# sch_Connet_IMU.net
KiCad netlist of a schematic drawn in Altium Designer
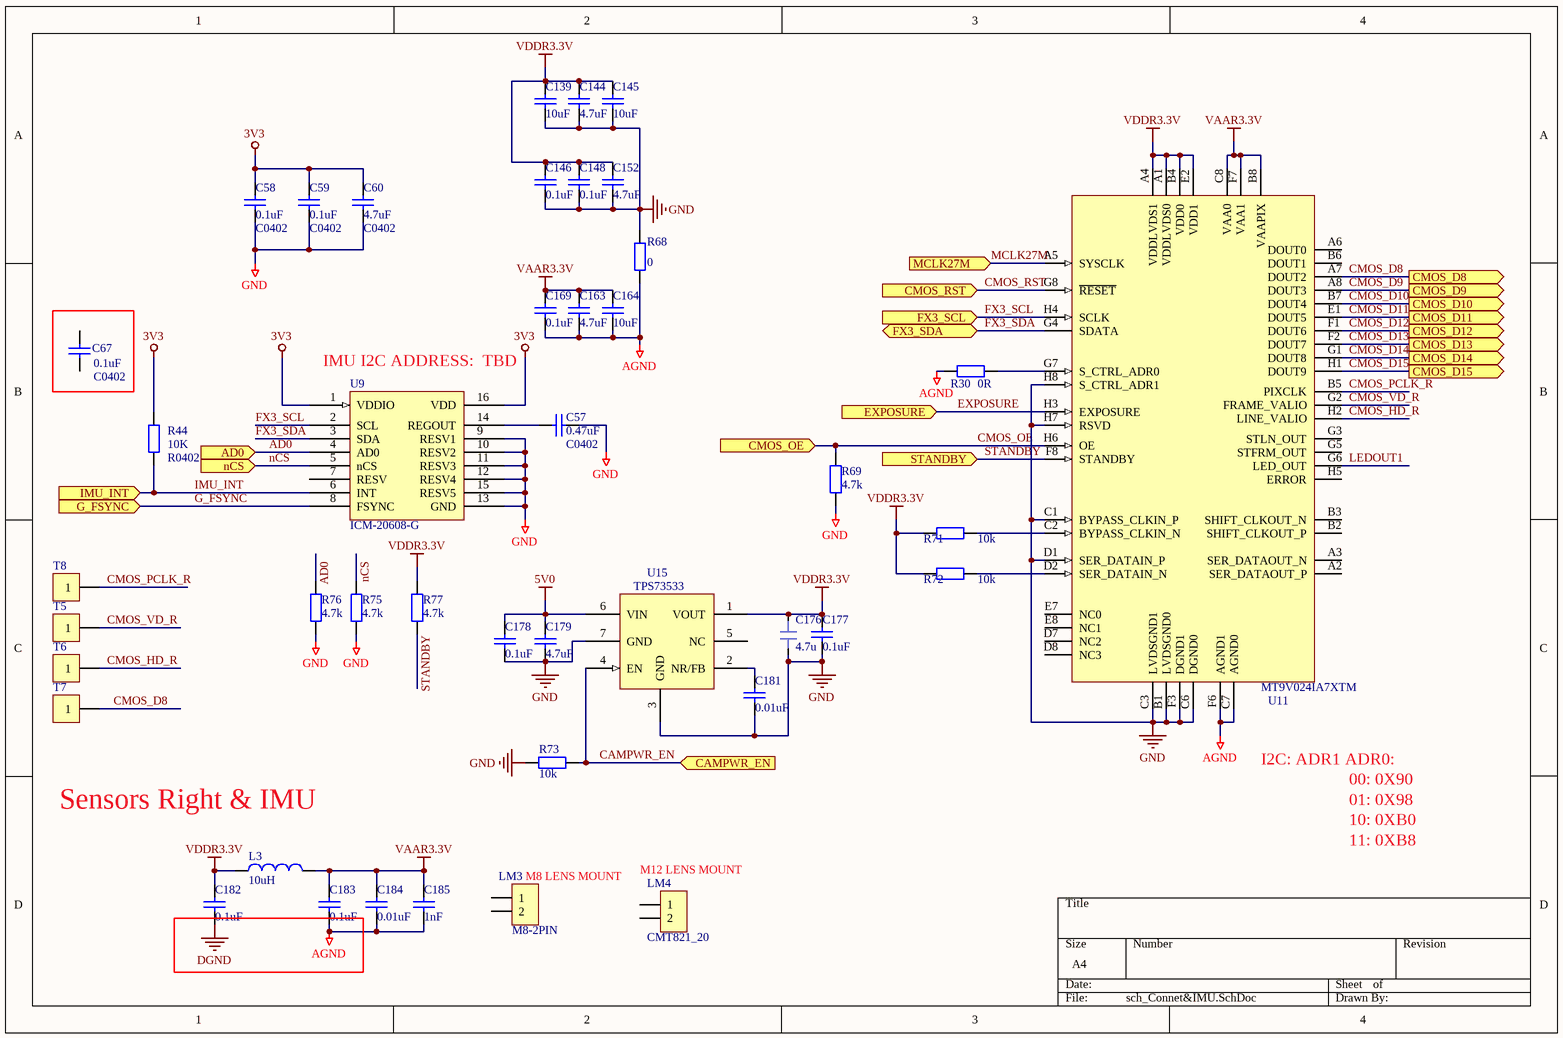
[diagram p0: sch_Connet&IMU.SchDoc]

(export (version "E")
  (design (tool "Eeschema 10.0.6"))
  (components
    (comp (ref "C57")
      (value "0.47uF")
      (footprint "0402C")
      (description "Capacitor")
      (fields (field (name "ALTIUM_VALUE") "C0402") (field (name "PUBLISHER") "Altium Limited"))
      (libsource (lib "Miscellaneous Devices") (part "Cap"))
    )
    (comp (ref "C58")
      (value "0.1uF")
      (footprint "0402C")
      (description "Capacitor")
      (fields (field (name "ALTIUM_VALUE") "C0402") (field (name "PUBLISHER") "Altium Limited"))
      (libsource (lib "Miscellaneous Devices") (part "Cap"))
    )
    (comp (ref "C59")
      (value "0.1uF")
      (footprint "0402C")
      (description "Capacitor")
      (fields (field (name "ALTIUM_VALUE") "C0402") (field (name "PUBLISHER") "Altium Limited"))
      (libsource (lib "Miscellaneous Devices") (part "Cap"))
    )
    (comp (ref "C60")
      (value "4.7uF")
      (footprint "0402C")
      (description "Capacitor")
      (fields (field (name "ALTIUM_VALUE") "C0402") (field (name "PUBLISHER") "Altium Limited"))
      (libsource (lib "Miscellaneous Devices") (part "Cap"))
    )
    (comp (ref "C67")
      (value "0.1uF")
      (footprint "0402C")
      (description "Capacitor")
      (fields (field (name "ALTIUM_VALUE") "C0402") (field (name "PUBLISHER") "Altium Limited"))
      (libsource (lib "Miscellaneous Devices") (part "Cap"))
    )
    (comp (ref "C139")
      (value "10uF")
      (footprint "0805C")
      (description "Capacitor")
      (fields (field (name "PUBLISHER") "Altium Limited"))
      (libsource (lib "Miscellaneous Devices") (part "Cap"))
    )
    (comp (ref "C144")
      (value "4.7uF")
      (footprint "0402C")
      (description "Capacitor")
      (fields (field (name "PUBLISHER") "Altium Limited"))
      (libsource (lib "Miscellaneous Devices") (part "Cap"))
    )
    (comp (ref "C145")
      (value "10uF")
      (footprint "0805C")
      (description "Capacitor")
      (fields (field (name "PUBLISHER") "Altium Limited"))
      (libsource (lib "Miscellaneous Devices") (part "Cap"))
    )
    (comp (ref "C146")
      (value "0.1uF")
      (footprint "0402C")
      (description "Capacitor")
      (fields (field (name "PUBLISHER") "Altium Limited"))
      (libsource (lib "Miscellaneous Devices") (part "Cap"))
    )
    (comp (ref "C148")
      (value "0.1uF")
      (footprint "0402C")
      (description "Capacitor")
      (fields (field (name "PUBLISHER") "Altium Limited"))
      (libsource (lib "Miscellaneous Devices") (part "Cap"))
    )
    (comp (ref "C152")
      (value "4.7uF")
      (footprint "0402C")
      (description "Capacitor")
      (fields (field (name "PUBLISHER") "Altium Limited"))
      (libsource (lib "Miscellaneous Devices") (part "Cap"))
    )
    (comp (ref "C163")
      (value "4.7uF")
      (footprint "0402C")
      (description "Capacitor")
      (fields (field (name "PUBLISHER") "Altium Limited"))
      (libsource (lib "Miscellaneous Devices") (part "Cap"))
    )
    (comp (ref "C164")
      (value "10uF")
      (footprint "0805C")
      (description "Capacitor")
      (fields (field (name "PUBLISHER") "Altium Limited"))
      (libsource (lib "Miscellaneous Devices") (part "Cap"))
    )
    (comp (ref "C169")
      (value "0.1uF")
      (footprint "0402C")
      (description "Capacitor")
      (fields (field (name "PUBLISHER") "Altium Limited"))
      (libsource (lib "Miscellaneous Devices") (part "Cap"))
    )
    (comp (ref "C176")
      (value "4.7u")
      (footprint "0402C_L")
      (description "CC0402MRX5R5BB475")
      (libsource (lib "V0P1") (part "cap0402"))
    )
    (comp (ref "C177")
      (value "0.1uF")
      (footprint "0402C_L")
      (description "Capacitor")
      (fields (field (name "PUBLISHER") "Altium Limited"))
      (libsource (lib "Miscellaneous Devices") (part "Cap"))
    )
    (comp (ref "C178")
      (value "0.1uF")
      (footprint "0402C")
      (description "Capacitor")
      (fields (field (name "PUBLISHER") "Altium Limited"))
      (libsource (lib "Miscellaneous Devices") (part "Cap"))
    )
    (comp (ref "C179")
      (value "4.7uF")
      (footprint "0402C_L")
      (description "Capacitor")
      (fields (field (name "PUBLISHER") "Altium Limited"))
      (libsource (lib "Miscellaneous Devices") (part "Cap"))
    )
    (comp (ref "C181")
      (value "0.01uF")
      (footprint "0402C_L")
      (description "Capacitor")
      (fields (field (name "PUBLISHER") "Altium Limited"))
      (libsource (lib "Miscellaneous Devices") (part "Cap"))
    )
    (comp (ref "C182")
      (value "0.1uF")
      (footprint "0402C_L")
      (description "Capacitor")
      (fields (field (name "PUBLISHER") "Altium Limited"))
      (libsource (lib "Miscellaneous Devices") (part "Cap"))
    )
    (comp (ref "C183")
      (value "0.1uF")
      (footprint "0402C_L")
      (description "Capacitor")
      (fields (field (name "PUBLISHER") "Altium Limited"))
      (libsource (lib "Miscellaneous Devices") (part "Cap"))
    )
    (comp (ref "C184")
      (value "0.01uF")
      (footprint "0402C_L")
      (description "Capacitor")
      (fields (field (name "PUBLISHER") "Altium Limited"))
      (libsource (lib "Miscellaneous Devices") (part "Cap"))
    )
    (comp (ref "C185")
      (value "1nF")
      (footprint "0402C_L")
      (description "Capacitor")
      (fields (field (name "PUBLISHER") "Altium Limited"))
      (libsource (lib "Miscellaneous Devices") (part "Cap"))
    )
    (comp (ref "L3")
      (value "10uH")
      (footprint "0805R")
      (description "Inductor")
      (libsource (lib "SWUST_ROBOT") (part "Inductor"))
    )
    (comp (ref "LM3")
      (value "M8-2PIN")
      (footprint "PAD_M3_D350_450")
      (description "Connector")
      (libsource (lib "SuperSchLib") (part "CON2"))
    )
    (comp (ref "LM4")
      (value "CMT821_20")
      (footprint "PAD_M3_D350_450")
      (description "Connector")
      (libsource (lib "SuperSchLib") (part "CON2"))
    )
    (comp (ref "R30")
      (value "0R")
      (footprint "0402R")
      (description "Resistor")
      (fields (field (name "PUBLISHER") "Altium Limited"))
      (libsource (lib "Miscellaneous Devices") (part "Res2"))
    )
    (comp (ref "R44")
      (value "10K")
      (footprint "0402R")
      (description "Resistor")
      (fields (field (name "ALTIUM_VALUE") "R0402") (field (name "PUBLISHER") "Altium Limited"))
      (libsource (lib "") (part "Res2_1"))
    )
    (comp (ref "R68")
      (value "0")
      (footprint "0402R")
      (description "Resistor")
      (fields (field (name "Comment") "0R") (field (name "PUBLISHER") "Altium Limited"))
      (libsource (lib "") (part "Resistor_2"))
    )
    (comp (ref "R69")
      (value "4.7k")
      (footprint "0402R_L")
      (description "Resistor")
      (fields (field (name "Comment") "4.7K") (field (name "PUBLISHER") "Altium Limited"))
      (libsource (lib "") (part "Resistor_1"))
    )
    (comp (ref "R71")
      (value "10k")
      (footprint "0402R")
      (description "Resistor")
      (fields (field (name "Comment") "10K") (field (name "PUBLISHER") "Altium Limited"))
      (libsource (lib "SZG") (part "Resistor"))
    )
    (comp (ref "R72")
      (value "10k")
      (footprint "0402R")
      (description "Resistor")
      (fields (field (name "Comment") "10K") (field (name "PUBLISHER") "Altium Limited"))
      (libsource (lib "SZG") (part "Resistor"))
    )
    (comp (ref "R73")
      (value "10k")
      (footprint "0402R_L")
      (description "Resistor")
      (fields (field (name "Comment") "10K") (field (name "PUBLISHER") "Altium Limited"))
      (libsource (lib "") (part "Resistor_1"))
    )
    (comp (ref "R75")
      (value "4.7k")
      (footprint "0402R")
      (description "Resistor")
      (fields (field (name "Comment") "4.7K") (field (name "PUBLISHER") "Altium Limited"))
      (libsource (lib "") (part "Resistor_1"))
    )
    (comp (ref "R76")
      (value "4.7k")
      (footprint "0402R")
      (description "Resistor")
      (fields (field (name "Comment") "4.7K") (field (name "PUBLISHER") "Altium Limited"))
      (libsource (lib "") (part "Resistor_1"))
    )
    (comp (ref "R77")
      (value "4.7k")
      (footprint "0402R")
      (description "Resistor")
      (fields (field (name "Comment") "4.7K") (field (name "PUBLISHER") "Altium Limited"))
      (libsource (lib "") (part "Resistor_1"))
    )
    (comp (ref "T5")
      (value "CON1")
      (footprint "PAD_TP_D1.2")
      (description "Connector")
      (libsource (lib "SuperSchLib") (part "CON1"))
    )
    (comp (ref "T6")
      (value "CON1")
      (footprint "PAD_TP_D1.2")
      (description "Connector")
      (libsource (lib "SuperSchLib") (part "CON1"))
    )
    (comp (ref "T7")
      (value "CON1")
      (footprint "PAD_TP_D1.2")
      (description "Connector")
      (libsource (lib "SuperSchLib") (part "CON1"))
    )
    (comp (ref "T8")
      (value "CON1")
      (footprint "PAD_TP_D1.2")
      (description "Connector")
      (libsource (lib "SuperSchLib") (part "CON1"))
    )
    (comp (ref "U9")
      (value "ICM-20608-G")
      (footprint "LGA16_P50L30W30H08")
      (libsource (lib "SZG") (part "ICM-20608-G"))
    )
    (comp (ref "U11")
      (value "MT9V024IA7XTM")
      (footprint "IBGA52_8X8_P100L90W90H90R")
      (libsource (lib "SZG") (part "MT9V024IA7XTM"))
    )
    (comp (ref "U15")
      (value "TPS73533")
      (footprint "SON6_P65L21W21H8_DRV")
      (libsource (lib "SZG") (part "TPS73533"))
    )
  )
  (nets
    (net (code "1") (name "/AD0") (class "Default")
      (node (ref "R76") (pin "2") (pinfunction "2_2") (pintype "passive"))
      (node (ref "U9") (pin "4") (pinfunction "AD0_4") (pintype "passive"))
    )
    (net (code "2") (name "/CAMPWR_EN") (class "Default")
      (node (ref "R73") (pin "2") (pinfunction "2_2") (pintype "passive"))
      (node (ref "U15") (pin "4") (pinfunction "EN_4") (pintype "input"))
    )
    (net (code "3") (name "/CMOS_D8") (class "Default")
      (node (ref "T7") (pin "1") (pinfunction "1_1") (pintype "passive"))
      (node (ref "U11") (pin "A7") (pinfunction "DOUT2_A7") (pintype "passive"))
    )
    (net (code "4") (name "/CMOS_D9") (class "Default")
      (node (ref "U11") (pin "A8") (pinfunction "DOUT3_A8") (pintype "passive"))
    )
    (net (code "5") (name "/CMOS_D10") (class "Default")
      (node (ref "U11") (pin "B7") (pinfunction "DOUT4_B7") (pintype "passive"))
    )
    (net (code "6") (name "/CMOS_D11") (class "Default")
      (node (ref "U11") (pin "E1") (pinfunction "DOUT5_E1") (pintype "passive"))
    )
    (net (code "7") (name "/CMOS_D12") (class "Default")
      (node (ref "U11") (pin "F1") (pinfunction "DOUT6_F1") (pintype "passive"))
    )
    (net (code "8") (name "/CMOS_D13") (class "Default")
      (node (ref "U11") (pin "F2") (pinfunction "DOUT7_F2") (pintype "passive"))
    )
    (net (code "9") (name "/CMOS_D14") (class "Default")
      (node (ref "U11") (pin "G1") (pinfunction "DOUT8_G1") (pintype "passive"))
    )
    (net (code "10") (name "/CMOS_D15") (class "Default")
      (node (ref "U11") (pin "H1") (pinfunction "DOUT9_H1") (pintype "passive"))
    )
    (net (code "11") (name "/CMOS_HD_R") (class "Default")
      (node (ref "T6") (pin "1") (pinfunction "1_1") (pintype "passive"))
      (node (ref "U11") (pin "H2") (pinfunction "LINE_VALIO_H2") (pintype "passive"))
    )
    (net (code "12") (name "/CMOS_OE") (class "Default")
      (node (ref "R69") (pin "2") (pinfunction "2_2") (pintype "passive"))
      (node (ref "U11") (pin "H6") (pinfunction "OE_H6") (pintype "input"))
    )
    (net (code "13") (name "/CMOS_PCLK_R") (class "Default")
      (node (ref "T8") (pin "1") (pinfunction "1_1") (pintype "passive"))
      (node (ref "U11") (pin "B5") (pinfunction "PIXCLK_B5") (pintype "passive"))
    )
    (net (code "14") (name "/CMOS_RST") (class "Default")
      (node (ref "U11") (pin "G8") (pinfunction "~{RESET}_G8") (pintype "input"))
    )
    (net (code "15") (name "/CMOS_VD_R") (class "Default")
      (node (ref "T5") (pin "1") (pinfunction "1_1") (pintype "passive"))
      (node (ref "U11") (pin "G2") (pinfunction "FRAME_VALIO_G2") (pintype "passive"))
    )
    (net (code "16") (name "/EXPOSURE") (class "Default")
      (node (ref "U11") (pin "H3") (pinfunction "EXPOSURE_H3") (pintype "input"))
    )
    (net (code "17") (name "/FX3_SCL") (class "Default")
      (node (ref "U11") (pin "H4") (pinfunction "SCLK_H4") (pintype "input"))
      (node (ref "U9") (pin "2") (pinfunction "SCL_2") (pintype "passive"))
    )
    (net (code "18") (name "/FX3_SDA") (class "Default")
      (node (ref "U11") (pin "G4") (pinfunction "SDATA_G4") (pintype "passive"))
      (node (ref "U9") (pin "3") (pinfunction "SDA_3") (pintype "passive"))
    )
    (net (code "19") (name "/G_FSYNC") (class "Default")
      (node (ref "U9") (pin "8") (pinfunction "FSYNC_8") (pintype "passive"))
    )
    (net (code "20") (name "/IMU_INT") (class "Default")
      (node (ref "R44") (pin "1") (pinfunction "1_1") (pintype "passive"))
      (node (ref "U9") (pin "6") (pinfunction "INT_6") (pintype "passive"))
    )
    (net (code "21") (name "/LEDOUT1") (class "Default")
      (node (ref "U11") (pin "G6") (pinfunction "LED_OUT_G6") (pintype "passive"))
    )
    (net (code "22") (name "/MCLK27M") (class "Default")
      (node (ref "U11") (pin "A5") (pinfunction "SYSCLK_A5") (pintype "input"))
    )
    (net (code "23") (name "/STANDBY") (class "Default")
      (node (ref "R77") (pin "1") (pinfunction "1_1") (pintype "passive"))
      (node (ref "U11") (pin "F8") (pinfunction "STANDBY_F8") (pintype "input"))
    )
    (net (code "24") (name "/nCS") (class "Default")
      (node (ref "R75") (pin "2") (pinfunction "2_2") (pintype "passive"))
      (node (ref "U9") (pin "5") (pinfunction "nCS_5") (pintype "passive"))
    )
    (net (code "25") (name "3V3") (class "Default")
      (node (ref "C58") (pin "2") (pinfunction "2_2") (pintype "passive"))
      (node (ref "C59") (pin "2") (pinfunction "2_2") (pintype "passive"))
      (node (ref "C60") (pin "2") (pinfunction "2_2") (pintype "passive"))
      (node (ref "R44") (pin "2") (pinfunction "2_2") (pintype "passive"))
      (node (ref "U9") (pin "1") (pinfunction "VDDIO_1") (pintype "input"))
      (node (ref "U9") (pin "16") (pinfunction "VDD_16") (pintype "passive"))
    )
    (net (code "26") (name "5V0") (class "Default")
      (node (ref "C178") (pin "2") (pinfunction "2_2") (pintype "passive"))
      (node (ref "C179") (pin "2") (pinfunction "2_2") (pintype "passive"))
      (node (ref "U15") (pin "6") (pinfunction "VIN_6") (pintype "passive"))
    )
    (net (code "27") (name "AGND") (class "Default")
      (node (ref "C163") (pin "1") (pinfunction "1_1") (pintype "passive"))
      (node (ref "C164") (pin "1") (pinfunction "1_1") (pintype "passive"))
      (node (ref "C169") (pin "1") (pinfunction "1_1") (pintype "passive"))
      (node (ref "C183") (pin "1") (pinfunction "1_1") (pintype "passive"))
      (node (ref "C184") (pin "1") (pinfunction "1_1") (pintype "passive"))
      (node (ref "C185") (pin "1") (pinfunction "1_1") (pintype "passive"))
      (node (ref "R30") (pin "2") (pinfunction "2_2") (pintype "passive"))
      (node (ref "R68") (pin "2") (pinfunction "2_2") (pintype "passive"))
      (node (ref "U11") (pin "C7") (pinfunction "AGND0_C7") (pintype "power_in"))
      (node (ref "U11") (pin "F6") (pinfunction "AGND1_F6") (pintype "power_in"))
    )
    (net (code "28") (name "DGND") (class "Default")
      (node (ref "C182") (pin "1") (pinfunction "1_1") (pintype "passive"))
    )
    (net (code "29") (name "GND") (class "Default")
      (node (ref "C139") (pin "1") (pinfunction "1_1") (pintype "passive"))
      (node (ref "C144") (pin "1") (pinfunction "1_1") (pintype "passive"))
      (node (ref "C145") (pin "1") (pinfunction "1_1") (pintype "passive"))
      (node (ref "C146") (pin "1") (pinfunction "1_1") (pintype "passive"))
      (node (ref "C148") (pin "1") (pinfunction "1_1") (pintype "passive"))
      (node (ref "C152") (pin "1") (pinfunction "1_1") (pintype "passive"))
      (node (ref "C176") (pin "2") (pinfunction "2_2") (pintype "passive"))
      (node (ref "C177") (pin "1") (pinfunction "1_1") (pintype "passive"))
      (node (ref "C178") (pin "1") (pinfunction "1_1") (pintype "passive"))
      (node (ref "C179") (pin "1") (pinfunction "1_1") (pintype "passive"))
      (node (ref "C181") (pin "1") (pinfunction "1_1") (pintype "passive"))
      (node (ref "C57") (pin "1") (pinfunction "1_1") (pintype "passive"))
      (node (ref "C58") (pin "1") (pinfunction "1_1") (pintype "passive"))
      (node (ref "C59") (pin "1") (pinfunction "1_1") (pintype "passive"))
      (node (ref "C60") (pin "1") (pinfunction "1_1") (pintype "passive"))
      (node (ref "R68") (pin "1") (pinfunction "1_1") (pintype "passive"))
      (node (ref "R69") (pin "1") (pinfunction "1_1") (pintype "passive"))
      (node (ref "R73") (pin "1") (pinfunction "1_1") (pintype "passive"))
      (node (ref "R75") (pin "1") (pinfunction "1_1") (pintype "passive"))
      (node (ref "R76") (pin "1") (pinfunction "1_1") (pintype "passive"))
      (node (ref "U11") (pin "B1") (pinfunction "LVDSGND0_B1") (pintype "power_in"))
      (node (ref "U11") (pin "C1") (pinfunction "BYPASS_CLKIN_P_C1") (pintype "input"))
      (node (ref "U11") (pin "C3") (pinfunction "LVDSGND1_C3") (pintype "power_in"))
      (node (ref "U11") (pin "C6") (pinfunction "DGND0_C6") (pintype "power_in"))
      (node (ref "U11") (pin "D1") (pinfunction "SER_DATAIN_P_D1") (pintype "input"))
      (node (ref "U11") (pin "F3") (pinfunction "DGND1_F3") (pintype "power_in"))
      (node (ref "U11") (pin "H7") (pinfunction "RSVD_H7") (pintype "input"))
      (node (ref "U11") (pin "H8") (pinfunction "S_CTRL_ADR1_H8") (pintype "input"))
      (node (ref "U15") (pin "3") (pinfunction "GND_3") (pintype "passive"))
      (node (ref "U15") (pin "7") (pinfunction "GND_7") (pintype "passive"))
      (node (ref "U9") (pin "10") (pinfunction "RESV2_10") (pintype "passive"))
      (node (ref "U9") (pin "11") (pinfunction "RESV3_11") (pintype "passive"))
      (node (ref "U9") (pin "12") (pinfunction "RESV4_12") (pintype "passive"))
      (node (ref "U9") (pin "13") (pinfunction "GND_13") (pintype "passive"))
      (node (ref "U9") (pin "15") (pinfunction "RESV5_15") (pintype "passive"))
      (node (ref "U9") (pin "9") (pinfunction "RESV1_9") (pintype "passive"))
    )
    (net (code "30") (name "Net-(U9-REGOUT)") (class "Default")
      (node (ref "C57") (pin "2") (pinfunction "2_2") (pintype "passive"))
      (node (ref "U9") (pin "14") (pinfunction "REGOUT_14") (pintype "passive"))
    )
    (net (code "31") (name "Net-(U11-BYPASS_CLKIN_N)") (class "Default")
      (node (ref "R71") (pin "1") (pinfunction "1_1") (pintype "passive"))
      (node (ref "U11") (pin "C2") (pinfunction "BYPASS_CLKIN_N_C2") (pintype "input"))
    )
    (net (code "32") (name "Net-(U11-SER_DATAIN_N)") (class "Default")
      (node (ref "R72") (pin "1") (pinfunction "1_1") (pintype "passive"))
      (node (ref "U11") (pin "D2") (pinfunction "SER_DATAIN_N_D2") (pintype "input"))
    )
    (net (code "33") (name "Net-(U11-S_CTRL_ADR0)") (class "Default")
      (node (ref "R30") (pin "1") (pinfunction "1_1") (pintype "passive"))
      (node (ref "U11") (pin "G7") (pinfunction "S_CTRL_ADR0_G7") (pintype "input"))
    )
    (net (code "34") (name "Net-(U15-NR{slash}FB)") (class "Default")
      (node (ref "C181") (pin "2") (pinfunction "2_2") (pintype "passive"))
      (node (ref "U15") (pin "2") (pinfunction "NR/FB_2") (pintype "passive"))
    )
    (net (code "35") (name "VAAR3.3V") (class "Default")
      (node (ref "C163") (pin "2") (pinfunction "2_2") (pintype "passive"))
      (node (ref "C164") (pin "2") (pinfunction "2_2") (pintype "passive"))
      (node (ref "C169") (pin "2") (pinfunction "2_2") (pintype "passive"))
      (node (ref "C183") (pin "2") (pinfunction "2_2") (pintype "passive"))
      (node (ref "C184") (pin "2") (pinfunction "2_2") (pintype "passive"))
      (node (ref "C185") (pin "2") (pinfunction "2_2") (pintype "passive"))
      (node (ref "L3") (pin "2") (pinfunction "2_2") (pintype "passive"))
      (node (ref "U11") (pin "B8") (pinfunction "VAAPIX_B8") (pintype "power_in"))
      (node (ref "U11") (pin "C8") (pinfunction "VAA0_C8") (pintype "power_in"))
      (node (ref "U11") (pin "F7") (pinfunction "VAA1_F7") (pintype "power_in"))
    )
    (net (code "36") (name "VDDR3.3V") (class "Default")
      (node (ref "C139") (pin "2") (pinfunction "2_2") (pintype "passive"))
      (node (ref "C144") (pin "2") (pinfunction "2_2") (pintype "passive"))
      (node (ref "C145") (pin "2") (pinfunction "2_2") (pintype "passive"))
      (node (ref "C146") (pin "2") (pinfunction "2_2") (pintype "passive"))
      (node (ref "C148") (pin "2") (pinfunction "2_2") (pintype "passive"))
      (node (ref "C152") (pin "2") (pinfunction "2_2") (pintype "passive"))
      (node (ref "C176") (pin "1") (pinfunction "1_1") (pintype "passive"))
      (node (ref "C177") (pin "2") (pinfunction "2_2") (pintype "passive"))
      (node (ref "C182") (pin "2") (pinfunction "2_2") (pintype "passive"))
      (node (ref "L3") (pin "1") (pinfunction "1_1") (pintype "passive"))
      (node (ref "R71") (pin "2") (pinfunction "2_2") (pintype "passive"))
      (node (ref "R72") (pin "2") (pinfunction "2_2") (pintype "passive"))
      (node (ref "R77") (pin "2") (pinfunction "2_2") (pintype "passive"))
      (node (ref "U11") (pin "A1") (pinfunction "VDDLVDS0_A1") (pintype "power_in"))
      (node (ref "U11") (pin "A4") (pinfunction "VDDLVDS1_A4") (pintype "power_in"))
      (node (ref "U11") (pin "B4") (pinfunction "VDD0_B4") (pintype "power_in"))
      (node (ref "U11") (pin "E2") (pinfunction "VDD1_E2") (pintype "power_in"))
      (node (ref "U15") (pin "1") (pinfunction "VOUT_1") (pintype "passive"))
    )
    (net (code "37") (name "unconnected-(C67-Pad1)") (class "Default")
      (node (ref "C67") (pin "1") (pinfunction "1_1") (pintype "passive"))
    )
    (net (code "38") (name "unconnected-(C67-Pad2)") (class "Default")
      (node (ref "C67") (pin "2") (pinfunction "2_2") (pintype "passive"))
    )
    (net (code "39") (name "unconnected-(LM3-Pad1)") (class "Default")
      (node (ref "LM3") (pin "1") (pinfunction "1_1") (pintype "passive"))
    )
    (net (code "40") (name "unconnected-(LM3-Pad2)") (class "Default")
      (node (ref "LM3") (pin "2") (pinfunction "2_2") (pintype "passive"))
    )
    (net (code "41") (name "unconnected-(LM4-Pad1)") (class "Default")
      (node (ref "LM4") (pin "1") (pinfunction "1_1") (pintype "passive"))
    )
    (net (code "42") (name "unconnected-(LM4-Pad2)") (class "Default")
      (node (ref "LM4") (pin "2") (pinfunction "2_2") (pintype "passive"))
    )
    (net (code "43") (name "unconnected-(U9-RESV-Pad7)") (class "Default")
      (node (ref "U9") (pin "7") (pinfunction "RESV_7") (pintype "passive"))
    )
    (net (code "44") (name "unconnected-(U11-DOUT0-PadA6)") (class "Default")
      (node (ref "U11") (pin "A6") (pinfunction "DOUT0_A6") (pintype "passive"))
    )
    (net (code "45") (name "unconnected-(U11-DOUT1-PadB6)") (class "Default")
      (node (ref "U11") (pin "B6") (pinfunction "DOUT1_B6") (pintype "passive"))
    )
    (net (code "46") (name "unconnected-(U11-ERROR-PadH5)") (class "Default")
      (node (ref "U11") (pin "H5") (pinfunction "ERROR_H5") (pintype "passive"))
    )
    (net (code "47") (name "unconnected-(U11-NC0-PadE7)") (class "Default")
      (node (ref "U11") (pin "E7") (pinfunction "NC0_E7") (pintype "passive"))
    )
    (net (code "48") (name "unconnected-(U11-NC1-PadE8)") (class "Default")
      (node (ref "U11") (pin "E8") (pinfunction "NC1_E8") (pintype "power_in"))
    )
    (net (code "49") (name "unconnected-(U11-NC2-PadD7)") (class "Default")
      (node (ref "U11") (pin "D7") (pinfunction "NC2_D7") (pintype "power_in"))
    )
    (net (code "50") (name "unconnected-(U11-NC3-PadD8)") (class "Default")
      (node (ref "U11") (pin "D8") (pinfunction "NC3_D8") (pintype "power_in"))
    )
    (net (code "51") (name "unconnected-(U11-SER_DATAOUT_N-PadA3)") (class "Default")
      (node (ref "U11") (pin "A3") (pinfunction "SER_DATAOUT_N_A3") (pintype "passive"))
    )
    (net (code "52") (name "unconnected-(U11-SER_DATAOUT_P-PadA2)") (class "Default")
      (node (ref "U11") (pin "A2") (pinfunction "SER_DATAOUT_P_A2") (pintype "passive"))
    )
    (net (code "53") (name "unconnected-(U11-SHIFT_CLKOUT_N-PadB3)") (class "Default")
      (node (ref "U11") (pin "B3") (pinfunction "SHIFT_CLKOUT_N_B3") (pintype "passive"))
    )
    (net (code "54") (name "unconnected-(U11-SHIFT_CLKOUT_P-PadB2)") (class "Default")
      (node (ref "U11") (pin "B2") (pinfunction "SHIFT_CLKOUT_P_B2") (pintype "passive"))
    )
    (net (code "55") (name "unconnected-(U11-STFRM_OUT-PadG5)") (class "Default")
      (node (ref "U11") (pin "G5") (pinfunction "STFRM_OUT_G5") (pintype "passive"))
    )
    (net (code "56") (name "unconnected-(U11-STLN_OUT-PadG3)") (class "Default")
      (node (ref "U11") (pin "G3") (pinfunction "STLN_OUT_G3") (pintype "passive"))
    )
    (net (code "57") (name "unconnected-(U15-NC-Pad5)") (class "Default")
      (node (ref "U15") (pin "5") (pinfunction "NC_5") (pintype "passive"))
    )
  )
)
